# Sheet2.net
KiCad netlist of a schematic drawn in Altium Designer
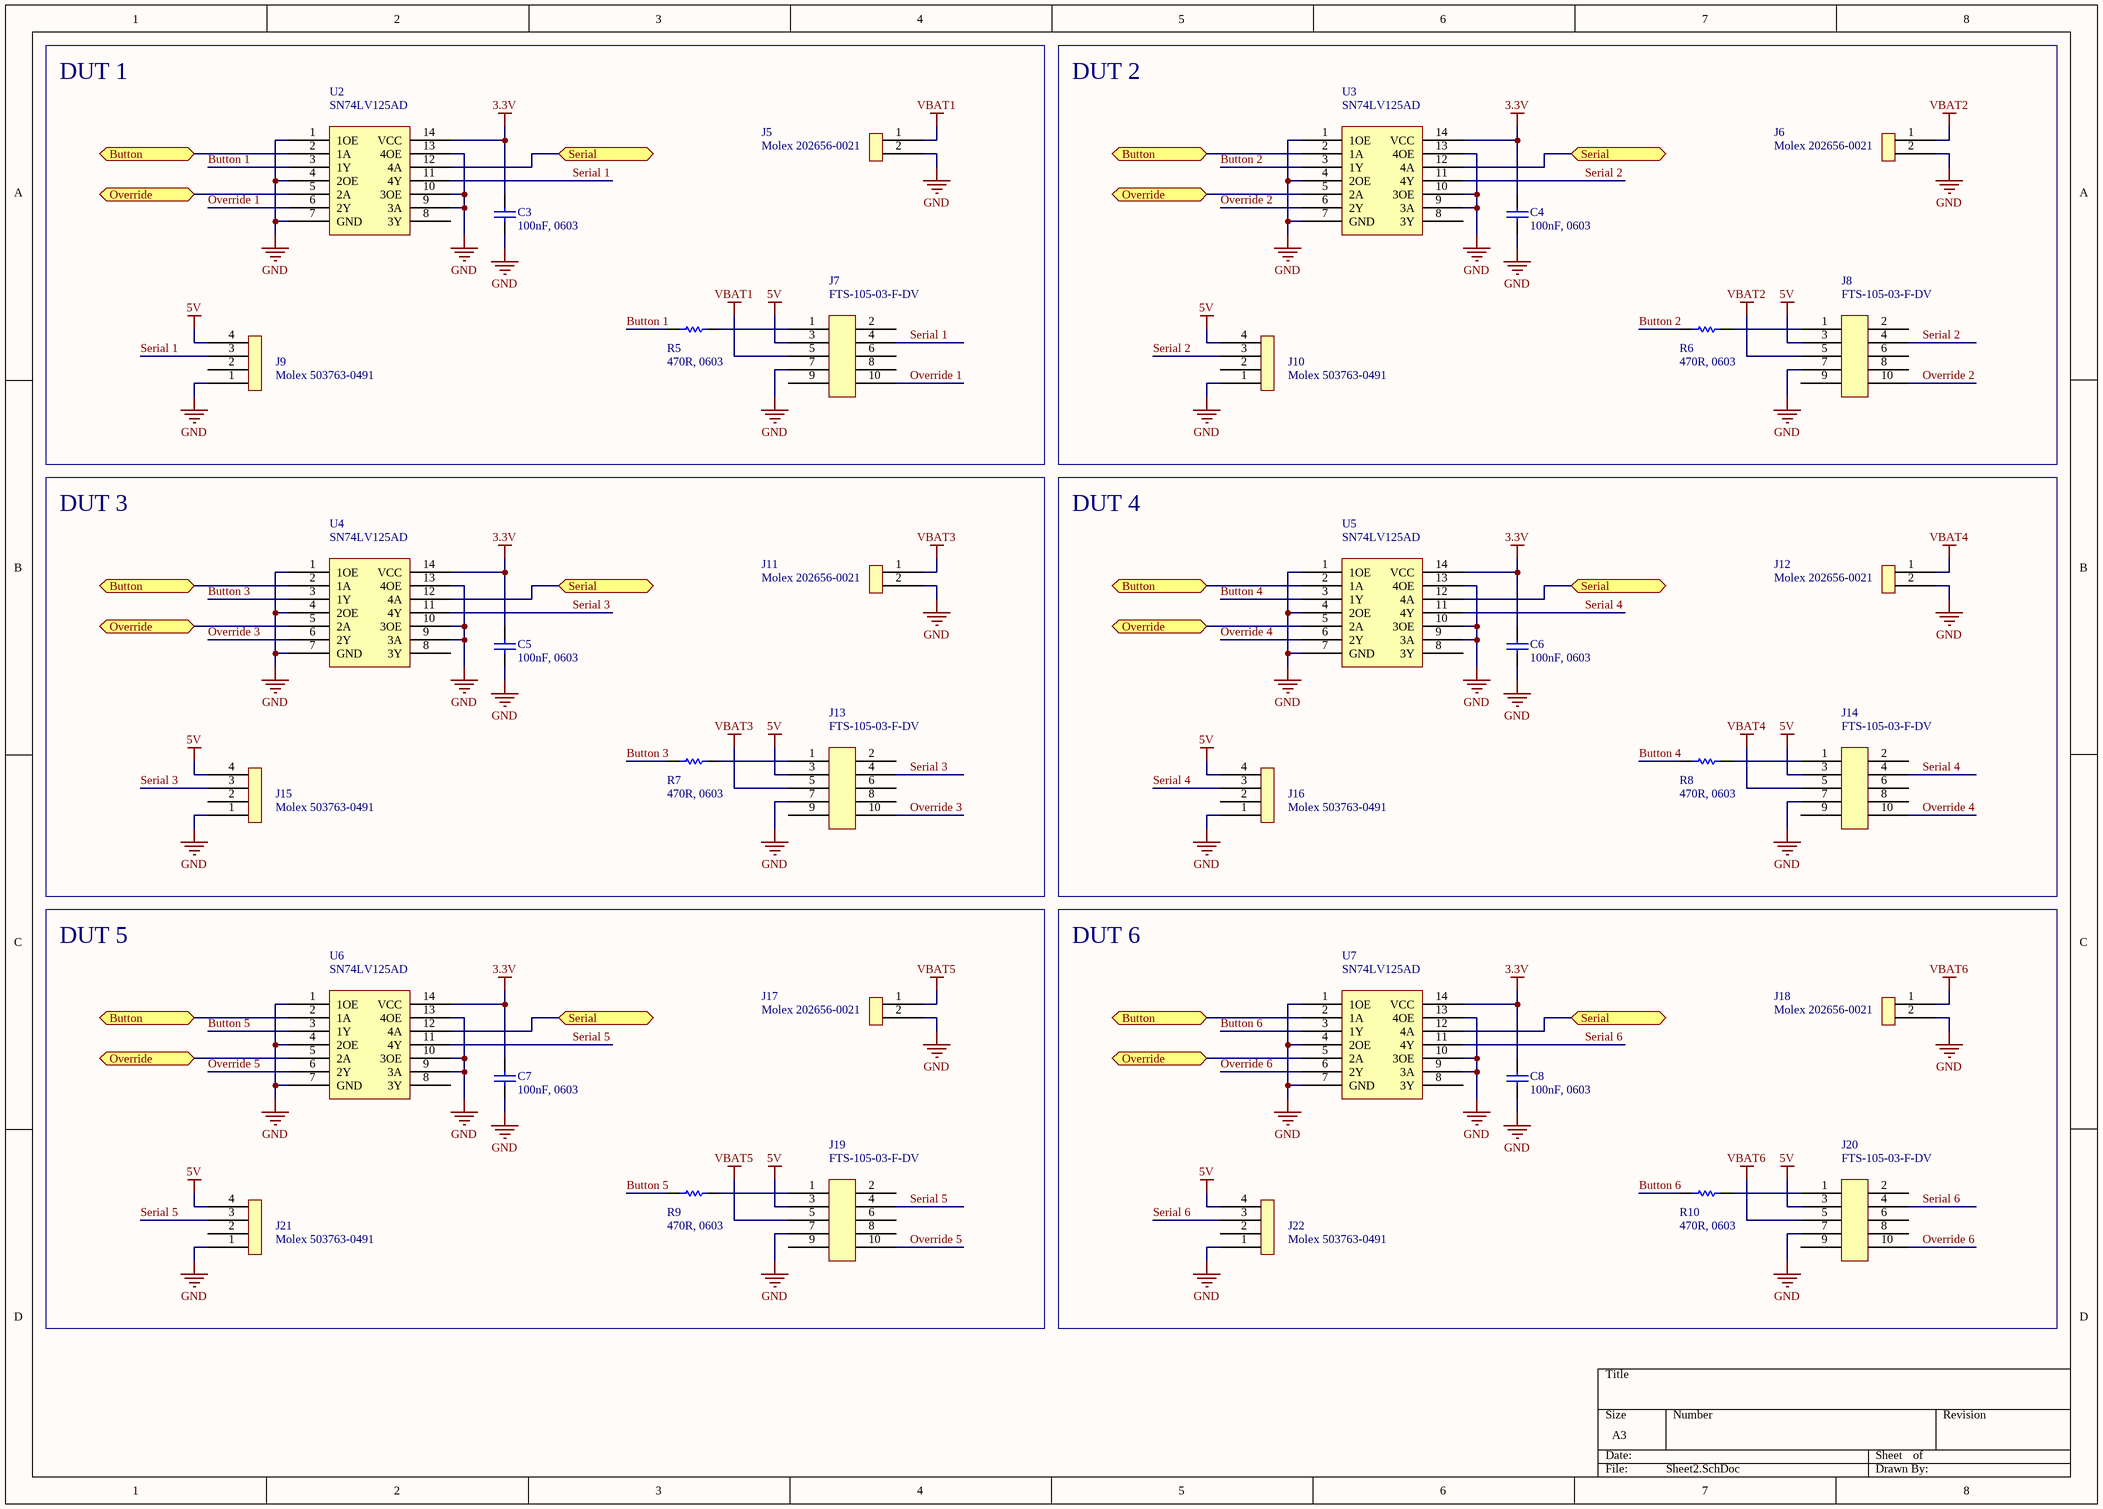
[diagram p0: Sheet2.SchDoc]

(export (version "E")
  (design (tool "Eeschema 10.0.6"))
  (components
    (comp (ref "C3")
      (value "100nF, 0603")
      (footprint "Capacitor 0603")
      (libsource (lib "x-io") (part "Capacitor"))
    )
    (comp (ref "C4")
      (value "100nF, 0603")
      (footprint "Capacitor 0603")
      (libsource (lib "x-io") (part "Capacitor"))
    )
    (comp (ref "C5")
      (value "100nF, 0603")
      (footprint "Capacitor 0603")
      (libsource (lib "x-io") (part "Capacitor"))
    )
    (comp (ref "C6")
      (value "100nF, 0603")
      (footprint "Capacitor 0603")
      (libsource (lib "x-io") (part "Capacitor"))
    )
    (comp (ref "C7")
      (value "100nF, 0603")
      (footprint "Capacitor 0603")
      (libsource (lib "x-io") (part "Capacitor"))
    )
    (comp (ref "C8")
      (value "100nF, 0603")
      (footprint "Capacitor 0603")
      (libsource (lib "x-io") (part "Capacitor"))
    )
    (comp (ref "J5")
      (value "Molex 202656-0021")
      (footprint "Molex 202656-0021")
      (libsource (lib "x-io") (part "Molex 202656-0021"))
    )
    (comp (ref "J6")
      (value "Molex 202656-0021")
      (footprint "Molex 202656-0021")
      (libsource (lib "x-io") (part "Molex 202656-0021"))
    )
    (comp (ref "J7")
      (value "FTS-105-03-F-DV")
      (footprint "FTS-105-03-F-DV")
      (libsource (lib "x-io") (part "FTS-105-03-F-DV"))
    )
    (comp (ref "J8")
      (value "FTS-105-03-F-DV")
      (footprint "FTS-105-03-F-DV")
      (libsource (lib "x-io") (part "FTS-105-03-F-DV"))
    )
    (comp (ref "J9")
      (value "Molex 503763-0491")
      (footprint "Molex 503763-0491")
      (libsource (lib "x-io") (part "Molex 503763-0491"))
    )
    (comp (ref "J10")
      (value "Molex 503763-0491")
      (footprint "Molex 503763-0491")
      (libsource (lib "x-io") (part "Molex 503763-0491"))
    )
    (comp (ref "J11")
      (value "Molex 202656-0021")
      (footprint "Molex 202656-0021")
      (libsource (lib "x-io") (part "Molex 202656-0021"))
    )
    (comp (ref "J12")
      (value "Molex 202656-0021")
      (footprint "Molex 202656-0021")
      (libsource (lib "x-io") (part "Molex 202656-0021"))
    )
    (comp (ref "J13")
      (value "FTS-105-03-F-DV")
      (footprint "FTS-105-03-F-DV")
      (libsource (lib "x-io") (part "FTS-105-03-F-DV"))
    )
    (comp (ref "J14")
      (value "FTS-105-03-F-DV")
      (footprint "FTS-105-03-F-DV")
      (libsource (lib "x-io") (part "FTS-105-03-F-DV"))
    )
    (comp (ref "J15")
      (value "Molex 503763-0491")
      (footprint "Molex 503763-0491")
      (libsource (lib "x-io") (part "Molex 503763-0491"))
    )
    (comp (ref "J16")
      (value "Molex 503763-0491")
      (footprint "Molex 503763-0491")
      (libsource (lib "x-io") (part "Molex 503763-0491"))
    )
    (comp (ref "J17")
      (value "Molex 202656-0021")
      (footprint "Molex 202656-0021")
      (libsource (lib "x-io") (part "Molex 202656-0021"))
    )
    (comp (ref "J18")
      (value "Molex 202656-0021")
      (footprint "Molex 202656-0021")
      (libsource (lib "x-io") (part "Molex 202656-0021"))
    )
    (comp (ref "J19")
      (value "FTS-105-03-F-DV")
      (footprint "FTS-105-03-F-DV")
      (libsource (lib "x-io") (part "FTS-105-03-F-DV"))
    )
    (comp (ref "J20")
      (value "FTS-105-03-F-DV")
      (footprint "FTS-105-03-F-DV")
      (libsource (lib "x-io") (part "FTS-105-03-F-DV"))
    )
    (comp (ref "J21")
      (value "Molex 503763-0491")
      (footprint "Molex 503763-0491")
      (libsource (lib "x-io") (part "Molex 503763-0491"))
    )
    (comp (ref "J22")
      (value "Molex 503763-0491")
      (footprint "Molex 503763-0491")
      (libsource (lib "x-io") (part "Molex 503763-0491"))
    )
    (comp (ref "R5")
      (value "470R, 0603")
      (footprint "Resistor 0603")
      (libsource (lib "x-io") (part "Resistor"))
    )
    (comp (ref "R6")
      (value "470R, 0603")
      (footprint "Resistor 0603")
      (libsource (lib "x-io") (part "Resistor"))
    )
    (comp (ref "R7")
      (value "470R, 0603")
      (footprint "Resistor 0603")
      (libsource (lib "x-io") (part "Resistor"))
    )
    (comp (ref "R8")
      (value "470R, 0603")
      (footprint "Resistor 0603")
      (libsource (lib "x-io") (part "Resistor"))
    )
    (comp (ref "R9")
      (value "470R, 0603")
      (footprint "Resistor 0603")
      (libsource (lib "x-io") (part "Resistor"))
    )
    (comp (ref "R10")
      (value "470R, 0603")
      (footprint "Resistor 0603")
      (libsource (lib "x-io") (part "Resistor"))
    )
    (comp (ref "U2")
      (value "SN74LV125AD")
      (footprint "SOIC-14")
      (libsource (lib "x-io") (part "SN74LVC125AD"))
    )
    (comp (ref "U3")
      (value "SN74LV125AD")
      (footprint "SOIC-14")
      (libsource (lib "x-io") (part "SN74LVC125AD"))
    )
    (comp (ref "U4")
      (value "SN74LV125AD")
      (footprint "SOIC-14")
      (libsource (lib "x-io") (part "SN74LVC125AD"))
    )
    (comp (ref "U5")
      (value "SN74LV125AD")
      (footprint "SOIC-14")
      (libsource (lib "x-io") (part "SN74LVC125AD"))
    )
    (comp (ref "U6")
      (value "SN74LV125AD")
      (footprint "SOIC-14")
      (libsource (lib "x-io") (part "SN74LVC125AD"))
    )
    (comp (ref "U7")
      (value "SN74LV125AD")
      (footprint "SOIC-14")
      (libsource (lib "x-io") (part "SN74LVC125AD"))
    )
  )
  (nets
    (net (code "1") (name "/Button") (class "Default")
      (node (ref "U2") (pin "2") (pinfunction "1A_2") (pintype "passive"))
      (node (ref "U3") (pin "2") (pinfunction "1A_2") (pintype "passive"))
      (node (ref "U4") (pin "2") (pinfunction "1A_2") (pintype "passive"))
      (node (ref "U5") (pin "2") (pinfunction "1A_2") (pintype "passive"))
      (node (ref "U6") (pin "2") (pinfunction "1A_2") (pintype "passive"))
      (node (ref "U7") (pin "2") (pinfunction "1A_2") (pintype "passive"))
    )
    (net (code "2") (name "/Button 1") (class "Default")
      (node (ref "R5") (pin "1") (pinfunction "1_1") (pintype "passive"))
      (node (ref "U2") (pin "3") (pinfunction "1Y_3") (pintype "passive"))
    )
    (net (code "3") (name "/Button 2") (class "Default")
      (node (ref "R6") (pin "1") (pinfunction "1_1") (pintype "passive"))
      (node (ref "U3") (pin "3") (pinfunction "1Y_3") (pintype "passive"))
    )
    (net (code "4") (name "/Button 3") (class "Default")
      (node (ref "R7") (pin "1") (pinfunction "1_1") (pintype "passive"))
      (node (ref "U4") (pin "3") (pinfunction "1Y_3") (pintype "passive"))
    )
    (net (code "5") (name "/Button 4") (class "Default")
      (node (ref "R8") (pin "1") (pinfunction "1_1") (pintype "passive"))
      (node (ref "U5") (pin "3") (pinfunction "1Y_3") (pintype "passive"))
    )
    (net (code "6") (name "/Button 5") (class "Default")
      (node (ref "R9") (pin "1") (pinfunction "1_1") (pintype "passive"))
      (node (ref "U6") (pin "3") (pinfunction "1Y_3") (pintype "passive"))
    )
    (net (code "7") (name "/Button 6") (class "Default")
      (node (ref "R10") (pin "1") (pinfunction "1_1") (pintype "passive"))
      (node (ref "U7") (pin "3") (pinfunction "1Y_3") (pintype "passive"))
    )
    (net (code "8") (name "/Override") (class "Default")
      (node (ref "U2") (pin "5") (pinfunction "2A_5") (pintype "passive"))
      (node (ref "U3") (pin "5") (pinfunction "2A_5") (pintype "passive"))
      (node (ref "U4") (pin "5") (pinfunction "2A_5") (pintype "passive"))
      (node (ref "U5") (pin "5") (pinfunction "2A_5") (pintype "passive"))
      (node (ref "U6") (pin "5") (pinfunction "2A_5") (pintype "passive"))
      (node (ref "U7") (pin "5") (pinfunction "2A_5") (pintype "passive"))
    )
    (net (code "9") (name "/Override 1") (class "Default")
      (node (ref "J7") (pin "10") (pinfunction "*_10") (pintype "passive"))
      (node (ref "U2") (pin "6") (pinfunction "2Y_6") (pintype "passive"))
    )
    (net (code "10") (name "/Override 2") (class "Default")
      (node (ref "J8") (pin "10") (pinfunction "*_10") (pintype "passive"))
      (node (ref "U3") (pin "6") (pinfunction "2Y_6") (pintype "passive"))
    )
    (net (code "11") (name "/Override 3") (class "Default")
      (node (ref "J13") (pin "10") (pinfunction "*_10") (pintype "passive"))
      (node (ref "U4") (pin "6") (pinfunction "2Y_6") (pintype "passive"))
    )
    (net (code "12") (name "/Override 4") (class "Default")
      (node (ref "J14") (pin "10") (pinfunction "*_10") (pintype "passive"))
      (node (ref "U5") (pin "6") (pinfunction "2Y_6") (pintype "passive"))
    )
    (net (code "13") (name "/Override 5") (class "Default")
      (node (ref "J19") (pin "10") (pinfunction "*_10") (pintype "passive"))
      (node (ref "U6") (pin "6") (pinfunction "2Y_6") (pintype "passive"))
    )
    (net (code "14") (name "/Override 6") (class "Default")
      (node (ref "J20") (pin "10") (pinfunction "*_10") (pintype "passive"))
      (node (ref "U7") (pin "6") (pinfunction "2Y_6") (pintype "passive"))
    )
    (net (code "15") (name "/Serial") (class "Default")
      (node (ref "U2") (pin "12") (pinfunction "4A_12") (pintype "passive"))
      (node (ref "U3") (pin "12") (pinfunction "4A_12") (pintype "passive"))
      (node (ref "U4") (pin "12") (pinfunction "4A_12") (pintype "passive"))
      (node (ref "U5") (pin "12") (pinfunction "4A_12") (pintype "passive"))
      (node (ref "U6") (pin "12") (pinfunction "4A_12") (pintype "passive"))
      (node (ref "U7") (pin "12") (pinfunction "4A_12") (pintype "passive"))
    )
    (net (code "16") (name "/Serial 1") (class "Default")
      (node (ref "J7") (pin "4") (pinfunction "*_4") (pintype "passive"))
      (node (ref "J9") (pin "3") (pinfunction "3_3") (pintype "passive"))
      (node (ref "U2") (pin "11") (pinfunction "4Y_11") (pintype "passive"))
    )
    (net (code "17") (name "/Serial 2") (class "Default")
      (node (ref "J10") (pin "3") (pinfunction "3_3") (pintype "passive"))
      (node (ref "J8") (pin "4") (pinfunction "*_4") (pintype "passive"))
      (node (ref "U3") (pin "11") (pinfunction "4Y_11") (pintype "passive"))
    )
    (net (code "18") (name "/Serial 3") (class "Default")
      (node (ref "J13") (pin "4") (pinfunction "*_4") (pintype "passive"))
      (node (ref "J15") (pin "3") (pinfunction "3_3") (pintype "passive"))
      (node (ref "U4") (pin "11") (pinfunction "4Y_11") (pintype "passive"))
    )
    (net (code "19") (name "/Serial 4") (class "Default")
      (node (ref "J14") (pin "4") (pinfunction "*_4") (pintype "passive"))
      (node (ref "J16") (pin "3") (pinfunction "3_3") (pintype "passive"))
      (node (ref "U5") (pin "11") (pinfunction "4Y_11") (pintype "passive"))
    )
    (net (code "20") (name "/Serial 5") (class "Default")
      (node (ref "J19") (pin "4") (pinfunction "*_4") (pintype "passive"))
      (node (ref "J21") (pin "3") (pinfunction "3_3") (pintype "passive"))
      (node (ref "U6") (pin "11") (pinfunction "4Y_11") (pintype "passive"))
    )
    (net (code "21") (name "/Serial 6") (class "Default")
      (node (ref "J20") (pin "4") (pinfunction "*_4") (pintype "passive"))
      (node (ref "J22") (pin "3") (pinfunction "3_3") (pintype "passive"))
      (node (ref "U7") (pin "11") (pinfunction "4Y_11") (pintype "passive"))
    )
    (net (code "22") (name "3.3V") (class "Default")
      (node (ref "C3") (pin "2") (pinfunction "2_2") (pintype "passive"))
      (node (ref "C4") (pin "2") (pinfunction "2_2") (pintype "passive"))
      (node (ref "C5") (pin "2") (pinfunction "2_2") (pintype "passive"))
      (node (ref "C6") (pin "2") (pinfunction "2_2") (pintype "passive"))
      (node (ref "C7") (pin "2") (pinfunction "2_2") (pintype "passive"))
      (node (ref "C8") (pin "2") (pinfunction "2_2") (pintype "passive"))
      (node (ref "U2") (pin "14") (pinfunction "VCC_14") (pintype "passive"))
      (node (ref "U3") (pin "14") (pinfunction "VCC_14") (pintype "passive"))
      (node (ref "U4") (pin "14") (pinfunction "VCC_14") (pintype "passive"))
      (node (ref "U5") (pin "14") (pinfunction "VCC_14") (pintype "passive"))
      (node (ref "U6") (pin "14") (pinfunction "VCC_14") (pintype "passive"))
      (node (ref "U7") (pin "14") (pinfunction "VCC_14") (pintype "passive"))
    )
    (net (code "23") (name "5V") (class "Default")
      (node (ref "J10") (pin "4") (pinfunction "4_4") (pintype "passive"))
      (node (ref "J13") (pin "3") (pinfunction "*_3") (pintype "passive"))
      (node (ref "J14") (pin "3") (pinfunction "*_3") (pintype "passive"))
      (node (ref "J15") (pin "4") (pinfunction "4_4") (pintype "passive"))
      (node (ref "J16") (pin "4") (pinfunction "4_4") (pintype "passive"))
      (node (ref "J19") (pin "3") (pinfunction "*_3") (pintype "passive"))
      (node (ref "J20") (pin "3") (pinfunction "*_3") (pintype "passive"))
      (node (ref "J21") (pin "4") (pinfunction "4_4") (pintype "passive"))
      (node (ref "J22") (pin "4") (pinfunction "4_4") (pintype "passive"))
      (node (ref "J7") (pin "3") (pinfunction "*_3") (pintype "passive"))
      (node (ref "J8") (pin "3") (pinfunction "*_3") (pintype "passive"))
      (node (ref "J9") (pin "4") (pinfunction "4_4") (pintype "passive"))
    )
    (net (code "24") (name "GND") (class "Default")
      (node (ref "C3") (pin "1") (pinfunction "1_1") (pintype "passive"))
      (node (ref "C4") (pin "1") (pinfunction "1_1") (pintype "passive"))
      (node (ref "C5") (pin "1") (pinfunction "1_1") (pintype "passive"))
      (node (ref "C6") (pin "1") (pinfunction "1_1") (pintype "passive"))
      (node (ref "C7") (pin "1") (pinfunction "1_1") (pintype "passive"))
      (node (ref "C8") (pin "1") (pinfunction "1_1") (pintype "passive"))
      (node (ref "J10") (pin "1") (pinfunction "1_1") (pintype "passive"))
      (node (ref "J11") (pin "2") (pinfunction "2_2") (pintype "passive"))
      (node (ref "J12") (pin "2") (pinfunction "2_2") (pintype "passive"))
      (node (ref "J13") (pin "7") (pinfunction "*_7") (pintype "passive"))
      (node (ref "J14") (pin "7") (pinfunction "*_7") (pintype "passive"))
      (node (ref "J15") (pin "1") (pinfunction "1_1") (pintype "passive"))
      (node (ref "J16") (pin "1") (pinfunction "1_1") (pintype "passive"))
      (node (ref "J17") (pin "2") (pinfunction "2_2") (pintype "passive"))
      (node (ref "J18") (pin "2") (pinfunction "2_2") (pintype "passive"))
      (node (ref "J19") (pin "7") (pinfunction "*_7") (pintype "passive"))
      (node (ref "J20") (pin "7") (pinfunction "*_7") (pintype "passive"))
      (node (ref "J21") (pin "1") (pinfunction "1_1") (pintype "passive"))
      (node (ref "J22") (pin "1") (pinfunction "1_1") (pintype "passive"))
      (node (ref "J5") (pin "2") (pinfunction "2_2") (pintype "passive"))
      (node (ref "J6") (pin "2") (pinfunction "2_2") (pintype "passive"))
      (node (ref "J7") (pin "7") (pinfunction "*_7") (pintype "passive"))
      (node (ref "J8") (pin "7") (pinfunction "*_7") (pintype "passive"))
      (node (ref "J9") (pin "1") (pinfunction "1_1") (pintype "passive"))
      (node (ref "U2") (pin "1") (pinfunction "1OE_1") (pintype "passive"))
      (node (ref "U2") (pin "10") (pinfunction "3OE_10") (pintype "passive"))
      (node (ref "U2") (pin "13") (pinfunction "4OE_13") (pintype "passive"))
      (node (ref "U2") (pin "4") (pinfunction "2OE_4") (pintype "passive"))
      (node (ref "U2") (pin "7") (pinfunction "GND_7") (pintype "passive"))
      (node (ref "U2") (pin "9") (pinfunction "3A_9") (pintype "passive"))
      (node (ref "U3") (pin "1") (pinfunction "1OE_1") (pintype "passive"))
      (node (ref "U3") (pin "10") (pinfunction "3OE_10") (pintype "passive"))
      (node (ref "U3") (pin "13") (pinfunction "4OE_13") (pintype "passive"))
      (node (ref "U3") (pin "4") (pinfunction "2OE_4") (pintype "passive"))
      (node (ref "U3") (pin "7") (pinfunction "GND_7") (pintype "passive"))
      (node (ref "U3") (pin "9") (pinfunction "3A_9") (pintype "passive"))
      (node (ref "U4") (pin "1") (pinfunction "1OE_1") (pintype "passive"))
      (node (ref "U4") (pin "10") (pinfunction "3OE_10") (pintype "passive"))
      (node (ref "U4") (pin "13") (pinfunction "4OE_13") (pintype "passive"))
      (node (ref "U4") (pin "4") (pinfunction "2OE_4") (pintype "passive"))
      (node (ref "U4") (pin "7") (pinfunction "GND_7") (pintype "passive"))
      (node (ref "U4") (pin "9") (pinfunction "3A_9") (pintype "passive"))
      (node (ref "U5") (pin "1") (pinfunction "1OE_1") (pintype "passive"))
      (node (ref "U5") (pin "10") (pinfunction "3OE_10") (pintype "passive"))
      (node (ref "U5") (pin "13") (pinfunction "4OE_13") (pintype "passive"))
      (node (ref "U5") (pin "4") (pinfunction "2OE_4") (pintype "passive"))
      (node (ref "U5") (pin "7") (pinfunction "GND_7") (pintype "passive"))
      (node (ref "U5") (pin "9") (pinfunction "3A_9") (pintype "passive"))
      (node (ref "U6") (pin "1") (pinfunction "1OE_1") (pintype "passive"))
      (node (ref "U6") (pin "10") (pinfunction "3OE_10") (pintype "passive"))
      (node (ref "U6") (pin "13") (pinfunction "4OE_13") (pintype "passive"))
      (node (ref "U6") (pin "4") (pinfunction "2OE_4") (pintype "passive"))
      (node (ref "U6") (pin "7") (pinfunction "GND_7") (pintype "passive"))
      (node (ref "U6") (pin "9") (pinfunction "3A_9") (pintype "passive"))
      (node (ref "U7") (pin "1") (pinfunction "1OE_1") (pintype "passive"))
      (node (ref "U7") (pin "10") (pinfunction "3OE_10") (pintype "passive"))
      (node (ref "U7") (pin "13") (pinfunction "4OE_13") (pintype "passive"))
      (node (ref "U7") (pin "4") (pinfunction "2OE_4") (pintype "passive"))
      (node (ref "U7") (pin "7") (pinfunction "GND_7") (pintype "passive"))
      (node (ref "U7") (pin "9") (pinfunction "3A_9") (pintype "passive"))
    )
    (net (code "25") (name "Net-(J7-*-Pad1)") (class "Default")
      (node (ref "J7") (pin "1") (pinfunction "*_1") (pintype "passive"))
      (node (ref "R5") (pin "2") (pinfunction "2_2") (pintype "passive"))
    )
    (net (code "26") (name "Net-(J8-*-Pad1)") (class "Default")
      (node (ref "J8") (pin "1") (pinfunction "*_1") (pintype "passive"))
      (node (ref "R6") (pin "2") (pinfunction "2_2") (pintype "passive"))
    )
    (net (code "27") (name "Net-(J13-*-Pad1)") (class "Default")
      (node (ref "J13") (pin "1") (pinfunction "*_1") (pintype "passive"))
      (node (ref "R7") (pin "2") (pinfunction "2_2") (pintype "passive"))
    )
    (net (code "28") (name "Net-(J14-*-Pad1)") (class "Default")
      (node (ref "J14") (pin "1") (pinfunction "*_1") (pintype "passive"))
      (node (ref "R8") (pin "2") (pinfunction "2_2") (pintype "passive"))
    )
    (net (code "29") (name "Net-(J19-*-Pad1)") (class "Default")
      (node (ref "J19") (pin "1") (pinfunction "*_1") (pintype "passive"))
      (node (ref "R9") (pin "2") (pinfunction "2_2") (pintype "passive"))
    )
    (net (code "30") (name "Net-(J20-*-Pad1)") (class "Default")
      (node (ref "J20") (pin "1") (pinfunction "*_1") (pintype "passive"))
      (node (ref "R10") (pin "2") (pinfunction "2_2") (pintype "passive"))
    )
    (net (code "31") (name "VBAT1") (class "Default")
      (node (ref "J5") (pin "1") (pinfunction "1_1") (pintype "passive"))
      (node (ref "J7") (pin "5") (pinfunction "*_5") (pintype "passive"))
    )
    (net (code "32") (name "VBAT2") (class "Default")
      (node (ref "J6") (pin "1") (pinfunction "1_1") (pintype "passive"))
      (node (ref "J8") (pin "5") (pinfunction "*_5") (pintype "passive"))
    )
    (net (code "33") (name "VBAT3") (class "Default")
      (node (ref "J11") (pin "1") (pinfunction "1_1") (pintype "passive"))
      (node (ref "J13") (pin "5") (pinfunction "*_5") (pintype "passive"))
    )
    (net (code "34") (name "VBAT4") (class "Default")
      (node (ref "J12") (pin "1") (pinfunction "1_1") (pintype "passive"))
      (node (ref "J14") (pin "5") (pinfunction "*_5") (pintype "passive"))
    )
    (net (code "35") (name "VBAT5") (class "Default")
      (node (ref "J17") (pin "1") (pinfunction "1_1") (pintype "passive"))
      (node (ref "J19") (pin "5") (pinfunction "*_5") (pintype "passive"))
    )
    (net (code "36") (name "VBAT6") (class "Default")
      (node (ref "J18") (pin "1") (pinfunction "1_1") (pintype "passive"))
      (node (ref "J20") (pin "5") (pinfunction "*_5") (pintype "passive"))
    )
    (net (code "37") (name "unconnected-(J7-*-Pad2)") (class "Default")
      (node (ref "J7") (pin "2") (pinfunction "*_2") (pintype "passive"))
    )
    (net (code "38") (name "unconnected-(J7-*-Pad6)") (class "Default")
      (node (ref "J7") (pin "6") (pinfunction "*_6") (pintype "passive"))
    )
    (net (code "39") (name "unconnected-(J7-*-Pad8)") (class "Default")
      (node (ref "J7") (pin "8") (pinfunction "*_8") (pintype "passive"))
    )
    (net (code "40") (name "unconnected-(J7-*-Pad9)") (class "Default")
      (node (ref "J7") (pin "9") (pinfunction "*_9") (pintype "passive"))
    )
    (net (code "41") (name "unconnected-(J8-*-Pad2)") (class "Default")
      (node (ref "J8") (pin "2") (pinfunction "*_2") (pintype "passive"))
    )
    (net (code "42") (name "unconnected-(J8-*-Pad6)") (class "Default")
      (node (ref "J8") (pin "6") (pinfunction "*_6") (pintype "passive"))
    )
    (net (code "43") (name "unconnected-(J8-*-Pad8)") (class "Default")
      (node (ref "J8") (pin "8") (pinfunction "*_8") (pintype "passive"))
    )
    (net (code "44") (name "unconnected-(J8-*-Pad9)") (class "Default")
      (node (ref "J8") (pin "9") (pinfunction "*_9") (pintype "passive"))
    )
    (net (code "45") (name "unconnected-(J9-Pad2)") (class "Default")
      (node (ref "J9") (pin "2") (pinfunction "2_2") (pintype "passive"))
    )
    (net (code "46") (name "unconnected-(J10-Pad2)") (class "Default")
      (node (ref "J10") (pin "2") (pinfunction "2_2") (pintype "passive"))
    )
    (net (code "47") (name "unconnected-(J13-*-Pad2)") (class "Default")
      (node (ref "J13") (pin "2") (pinfunction "*_2") (pintype "passive"))
    )
    (net (code "48") (name "unconnected-(J13-*-Pad6)") (class "Default")
      (node (ref "J13") (pin "6") (pinfunction "*_6") (pintype "passive"))
    )
    (net (code "49") (name "unconnected-(J13-*-Pad8)") (class "Default")
      (node (ref "J13") (pin "8") (pinfunction "*_8") (pintype "passive"))
    )
    (net (code "50") (name "unconnected-(J13-*-Pad9)") (class "Default")
      (node (ref "J13") (pin "9") (pinfunction "*_9") (pintype "passive"))
    )
    (net (code "51") (name "unconnected-(J14-*-Pad2)") (class "Default")
      (node (ref "J14") (pin "2") (pinfunction "*_2") (pintype "passive"))
    )
    (net (code "52") (name "unconnected-(J14-*-Pad6)") (class "Default")
      (node (ref "J14") (pin "6") (pinfunction "*_6") (pintype "passive"))
    )
    (net (code "53") (name "unconnected-(J14-*-Pad8)") (class "Default")
      (node (ref "J14") (pin "8") (pinfunction "*_8") (pintype "passive"))
    )
    (net (code "54") (name "unconnected-(J14-*-Pad9)") (class "Default")
      (node (ref "J14") (pin "9") (pinfunction "*_9") (pintype "passive"))
    )
    (net (code "55") (name "unconnected-(J15-Pad2)") (class "Default")
      (node (ref "J15") (pin "2") (pinfunction "2_2") (pintype "passive"))
    )
    (net (code "56") (name "unconnected-(J16-Pad2)") (class "Default")
      (node (ref "J16") (pin "2") (pinfunction "2_2") (pintype "passive"))
    )
    (net (code "57") (name "unconnected-(J19-*-Pad2)") (class "Default")
      (node (ref "J19") (pin "2") (pinfunction "*_2") (pintype "passive"))
    )
    (net (code "58") (name "unconnected-(J19-*-Pad6)") (class "Default")
      (node (ref "J19") (pin "6") (pinfunction "*_6") (pintype "passive"))
    )
    (net (code "59") (name "unconnected-(J19-*-Pad8)") (class "Default")
      (node (ref "J19") (pin "8") (pinfunction "*_8") (pintype "passive"))
    )
    (net (code "60") (name "unconnected-(J19-*-Pad9)") (class "Default")
      (node (ref "J19") (pin "9") (pinfunction "*_9") (pintype "passive"))
    )
    (net (code "61") (name "unconnected-(J20-*-Pad2)") (class "Default")
      (node (ref "J20") (pin "2") (pinfunction "*_2") (pintype "passive"))
    )
    (net (code "62") (name "unconnected-(J20-*-Pad6)") (class "Default")
      (node (ref "J20") (pin "6") (pinfunction "*_6") (pintype "passive"))
    )
    (net (code "63") (name "unconnected-(J20-*-Pad8)") (class "Default")
      (node (ref "J20") (pin "8") (pinfunction "*_8") (pintype "passive"))
    )
    (net (code "64") (name "unconnected-(J20-*-Pad9)") (class "Default")
      (node (ref "J20") (pin "9") (pinfunction "*_9") (pintype "passive"))
    )
    (net (code "65") (name "unconnected-(J21-Pad2)") (class "Default")
      (node (ref "J21") (pin "2") (pinfunction "2_2") (pintype "passive"))
    )
    (net (code "66") (name "unconnected-(J22-Pad2)") (class "Default")
      (node (ref "J22") (pin "2") (pinfunction "2_2") (pintype "passive"))
    )
    (net (code "67") (name "unconnected-(U2-3Y-Pad8)") (class "Default")
      (node (ref "U2") (pin "8") (pinfunction "3Y_8") (pintype "passive"))
    )
    (net (code "68") (name "unconnected-(U3-3Y-Pad8)") (class "Default")
      (node (ref "U3") (pin "8") (pinfunction "3Y_8") (pintype "passive"))
    )
    (net (code "69") (name "unconnected-(U4-3Y-Pad8)") (class "Default")
      (node (ref "U4") (pin "8") (pinfunction "3Y_8") (pintype "passive"))
    )
    (net (code "70") (name "unconnected-(U5-3Y-Pad8)") (class "Default")
      (node (ref "U5") (pin "8") (pinfunction "3Y_8") (pintype "passive"))
    )
    (net (code "71") (name "unconnected-(U6-3Y-Pad8)") (class "Default")
      (node (ref "U6") (pin "8") (pinfunction "3Y_8") (pintype "passive"))
    )
    (net (code "72") (name "unconnected-(U7-3Y-Pad8)") (class "Default")
      (node (ref "U7") (pin "8") (pinfunction "3Y_8") (pintype "passive"))
    )
  )
)
